# ch347.net
KiCad netlist of a schematic drawn in Altium Designer
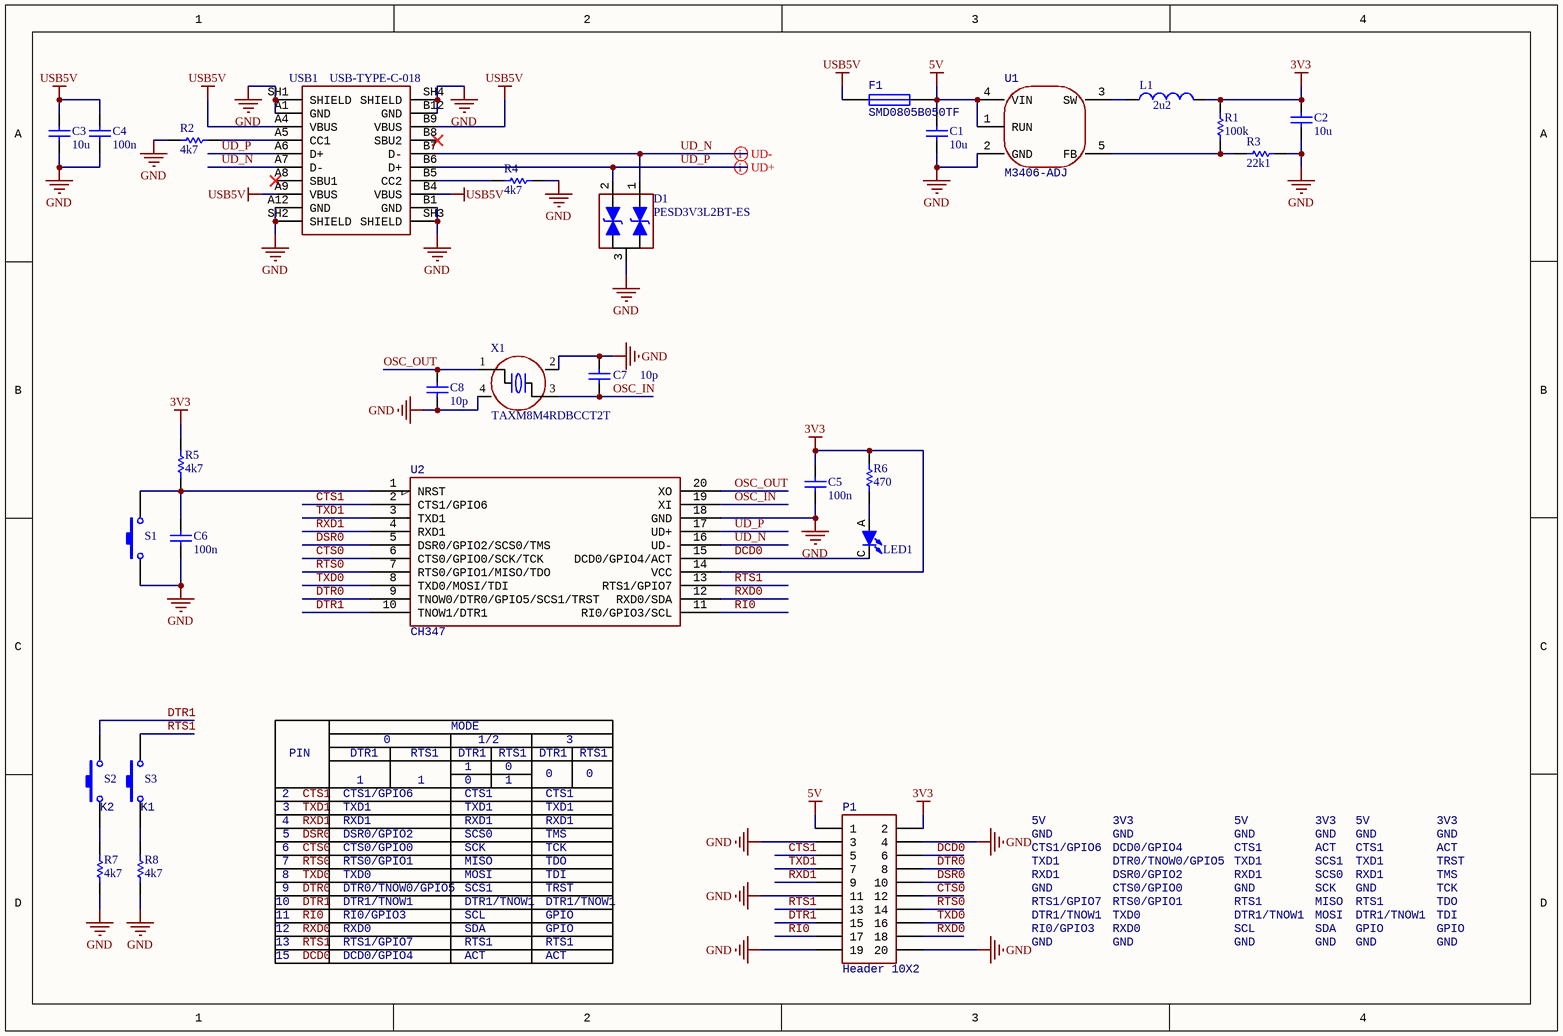
[diagram p0: ch347.SchDoc]

(export (version "E")
  (design (tool "Eeschema 10.0.6"))
  (components
    (comp (ref "C1")
      (value "10u")
      (footprint "footprints:CAPC160X80X90L30N")
      (fields
        (field (name "MPN") "TCC0603X5R106K100CT")
        (field (name "MANUFACTURER") "CCTC(三环)")
        (field (name "Comment") "Capacitor")
      )
      (libsource (lib "std_lib") (part "Capacitor"))
    )
    (comp (ref "C2")
      (value "10u")
      (footprint "footprints:CAPC160X80X90L30N")
      (fields
        (field (name "MPN") "TCC0603X5R106K100CT")
        (field (name "MANUFACTURER") "CCTC(三环)")
        (field (name "Comment") "Capacitor")
      )
      (libsource (lib "std_lib") (part "Capacitor"))
    )
    (comp (ref "C3")
      (value "10u")
      (footprint "footprints:CAPC160X80X90L30N")
      (fields
        (field (name "MPN") "TCC0603X5R106K100CT")
        (field (name "MANUFACTURER") "CCTC(三环)")
        (field (name "Comment") "Capacitor")
      )
      (libsource (lib "std_lib") (part "Capacitor"))
    )
    (comp (ref "C4")
      (value "100n")
      (footprint "footprints:CAPC100X50X55L25N")
      (fields
        (field (name "MPN") "TCC0402X5R104M250AT")
        (field (name "MANUFACTURER") "CCTC(三环)")
        (field (name "Comment") "Capacitor")
      )
      (libsource (lib "std_lib") (part "Capacitor"))
    )
    (comp (ref "C5")
      (value "100n")
      (footprint "footprints:CAPC100X50X55L25N")
      (fields
        (field (name "MPN") "TCC0402X5R104M250AT")
        (field (name "MANUFACTURER") "CCTC(三环)")
        (field (name "Comment") "Capacitor")
      )
      (libsource (lib "std_lib") (part "Capacitor"))
    )
    (comp (ref "C6")
      (value "100n")
      (footprint "footprints:CAPC100X50X55L25N")
      (fields
        (field (name "MPN") "TCC0402X5R104M250AT")
        (field (name "MANUFACTURER") "CCTC(三环)")
        (field (name "Comment") "Capacitor")
      )
      (libsource (lib "std_lib") (part "Capacitor"))
    )
    (comp (ref "C7")
      (value "10p")
      (footprint "footprints:CAPC100X50X55L25N")
      (fields
        (field (name "MPN") "CC0402JRNPO9BN100")
        (field (name "MANUFACTURER") "YAGEO(国巨)")
        (field (name "Comment") "Capacitor")
      )
      (libsource (lib "std_lib") (part "Capacitor"))
    )
    (comp (ref "C8")
      (value "10p")
      (footprint "footprints:CAPC100X50X55L25N")
      (fields
        (field (name "MPN") "CC0402JRNPO9BN100")
        (field (name "MANUFACTURER") "YAGEO(国巨)")
        (field (name "Comment") "Capacitor")
      )
      (libsource (lib "std_lib") (part "Capacitor"))
    )
    (comp (ref "D1")
      (value "PESD3V3L2BT-ES")
      (footprint "footprints:SOT23-3P95_237X111L52X43N")
      (description "2路双向ESD")
      (fields (field (name "MANUFACTURER") "ElecSuper(静芯微)"))
      (libsource (lib "mcontroller") (part "SMC24"))
    )
    (comp (ref "F1")
      (value "SMD0805B050TF")
      (footprint "footprints:FUSC210X135X125L37N")
      (description "Fuse")
      (libsource (lib "Miscellaneous Devices") (part "Fuse 1"))
    )
    (comp (ref "L1")
      (value "2u2")
      (footprint "footprints:INDC200X160X105L60N")
      (fields
        (field (name "MPN") "SFE201610-2R2M")
        (field (name "MANUFACTURER") "DDY(德立)")
        (field (name "Comment") "Inductor")
      )
      (libsource (lib "std_lib") (part "Inductor"))
    )
    (comp (ref "LED1")
      (value "蓝灯 正贴")
      (footprint "footprints:LEDC100X50X45L25N")
      (description "贴片LED")
      (libsource (lib "mcontroller") (part "LED-SMD"))
    )
    (comp (ref "P1")
      (value "Header 10X2")
      (footprint "footprints:HDRV20W63P254_10X2_2540X508H860")
      (description "Header, 10-Pin, Dual row")
      (libsource (lib "Sch") (part "Header 10X2"))
    )
    (comp (ref "R1")
      (value "100k")
      (footprint "footprints:RESC100X50X35L25N")
      (fields
        (field (name "MPN") "RTT021003FTH")
        (field (name "MANUFACTURER") "RALEC(旺诠)")
        (field (name "Comment") "Resistor")
      )
      (libsource (lib "std_lib") (part "Resistor"))
    )
    (comp (ref "R2")
      (value "4k7")
      (footprint "footprints:RESC100X50X35L25N")
      (fields
        (field (name "MPN") "RTT02472JTH")
        (field (name "MANUFACTURER") "RALEC(旺诠)")
        (field (name "Comment") "Resistor")
      )
      (libsource (lib "std_lib") (part "Resistor"))
    )
    (comp (ref "R3")
      (value "22k1")
      (footprint "footprints:RESC100X50X35L25N")
      (fields
        (field (name "MPN") "RTT022212FTH")
        (field (name "MANUFACTURER") "RALEC(旺诠)")
        (field (name "Comment") "Resistor")
      )
      (libsource (lib "std_lib") (part "Resistor"))
    )
    (comp (ref "R4")
      (value "4k7")
      (footprint "footprints:RESC100X50X35L25N")
      (fields
        (field (name "MPN") "RTT02472JTH")
        (field (name "MANUFACTURER") "RALEC(旺诠)")
        (field (name "Comment") "Resistor")
      )
      (libsource (lib "std_lib") (part "Resistor"))
    )
    (comp (ref "R5")
      (value "4k7")
      (footprint "footprints:RESC100X50X35L25N")
      (fields
        (field (name "MPN") "RTT02472JTH")
        (field (name "MANUFACTURER") "RALEC(旺诠)")
        (field (name "Comment") "Resistor")
      )
      (libsource (lib "std_lib") (part "Resistor"))
    )
    (comp (ref "R6")
      (value "470")
      (footprint "footprints:RESC100X50X35L25N")
      (fields
        (field (name "MPN") "RTT02471JTH")
        (field (name "MANUFACTURER") "RALEC(旺诠)")
        (field (name "Comment") "Resistor")
      )
      (libsource (lib "std_lib") (part "Resistor"))
    )
    (comp (ref "R7")
      (value "4k7")
      (footprint "footprints:RESC100X50X35L25N")
      (fields
        (field (name "MPN") "RTT02472JTH")
        (field (name "MANUFACTURER") "RALEC(旺诠)")
        (field (name "Comment") "Resistor")
      )
      (libsource (lib "std_lib") (part "Resistor"))
    )
    (comp (ref "R8")
      (value "4k7")
      (footprint "footprints:RESC100X50X35L25N")
      (fields
        (field (name "MPN") "RTT02472JTH")
        (field (name "MANUFACTURER") "RALEC(旺诠)")
        (field (name "Comment") "Resistor")
      )
      (libsource (lib "std_lib") (part "Resistor"))
    )
    (comp (ref "S1")
      (value "KEY")
      (footprint "footprints:RESRR450W70L600T345H610")
      (description "Switch")
      (libsource (lib "Miscellaneous Devices") (part "SW-PB"))
    )
    (comp (ref "S2")
      (value "KEY")
      (footprint "footprints:RESRR450W70L600T345H610")
      (description "Switch")
      (libsource (lib "Miscellaneous Devices") (part "SW-PB"))
    )
    (comp (ref "S3")
      (value "KEY")
      (footprint "footprints:RESRR450W70L600T345H610")
      (description "Switch")
      (libsource (lib "Miscellaneous Devices") (part "SW-PB"))
    )
    (comp (ref "U1")
      (value "M3406-ADJ")
      (footprint "footprints:SOT23-5P95_280X110L37X40N")
      (description "Vin=2V~6V,800mA,DCDC")
      (fields (field (name "MANUFACTURER") "西安航天民芯"))
      (libsource (lib "Sch") (part "M3406-ADJ"))
    )
    (comp (ref "U2")
      (value "CH347")
      (footprint "Pcb:SOP20P65_650X640X120L60X24N")
      (libsource (lib "Sch") (part "CH347"))
    )
    (comp (ref "USB1")
      (value "USB-TYPE-C-018")
      (footprint "footprints:USB-TYPE-C-018")
      (libsource (lib "Sch") (part "USB-TYPE-C-018"))
    )
    (comp (ref "X1")
      (value "TAXM8M4RDBCCT2T")
      (footprint "footprints:OSCCC320X250X80L90X100N")
      (description "8MHz ±10ppm 10pF")
      (fields (field (name "MANUFACTURER") "TAE(雅晶鑫)"))
      (libsource (lib "mcontroller") (part "X32258MSB4SI"))
    )
  )
  (nets
    (net (code "1") (name "/CTS0") (class "Default")
      (node (ref "P1") (pin "12") (pinfunction "12_12") (pintype "passive"))
      (node (ref "U2") (pin "6") (pinfunction "CTS0/GPIO0/SCK/TCK_6") (pintype "passive"))
    )
    (net (code "2") (name "/CTS1") (class "Default")
      (node (ref "P1") (pin "5") (pinfunction "5_5") (pintype "passive"))
      (node (ref "U2") (pin "2") (pinfunction "CTS1/GPIO6_2") (pintype "passive"))
    )
    (net (code "3") (name "/DCD0") (class "Default")
      (node (ref "LED1") (pin "C") (pinfunction "K_C") (pintype "passive"))
      (node (ref "P1") (pin "6") (pinfunction "6_6") (pintype "passive"))
      (node (ref "U2") (pin "15") (pinfunction "DCD0/GPIO4/ACT_15") (pintype "passive"))
    )
    (net (code "4") (name "/DSR0") (class "Default")
      (node (ref "P1") (pin "10") (pinfunction "10_10") (pintype "passive"))
      (node (ref "U2") (pin "5") (pinfunction "DSR0/GPIO2/SCS0/TMS_5") (pintype "passive"))
    )
    (net (code "5") (name "/DTR0") (class "Default")
      (node (ref "P1") (pin "8") (pinfunction "8_8") (pintype "passive"))
      (node (ref "U2") (pin "9") (pinfunction "TNOW0/DTR0/GPIO5/SCS1/TRST_9") (pintype "passive"))
    )
    (net (code "6") (name "/DTR1") (class "Default")
      (node (ref "P1") (pin "15") (pinfunction "15_15") (pintype "passive"))
      (node (ref "S2") (pin "1") (pinfunction "1_1") (pintype "passive"))
      (node (ref "U2") (pin "10") (pinfunction "TNOW1/DTR1_10") (pintype "passive"))
    )
    (net (code "7") (name "/OSC_IN") (class "Default")
      (node (ref "C7") (pin "1") (pinfunction "1_1") (pintype "passive"))
      (node (ref "U2") (pin "19") (pinfunction "XI_19") (pintype "passive"))
      (node (ref "X1") (pin "3") (pinfunction "3_3") (pintype "passive"))
    )
    (net (code "8") (name "/OSC_OUT") (class "Default")
      (node (ref "C8") (pin "2") (pinfunction "2_2") (pintype "passive"))
      (node (ref "U2") (pin "20") (pinfunction "XO_20") (pintype "passive"))
      (node (ref "X1") (pin "1") (pinfunction "1_1") (pintype "passive"))
    )
    (net (code "9") (name "/RI0") (class "Default")
      (node (ref "P1") (pin "17") (pinfunction "17_17") (pintype "passive"))
      (node (ref "U2") (pin "11") (pinfunction "RI0/GPIO3/SCL_11") (pintype "passive"))
    )
    (net (code "10") (name "/RTS0") (class "Default")
      (node (ref "P1") (pin "14") (pinfunction "14_14") (pintype "passive"))
      (node (ref "U2") (pin "7") (pinfunction "RTS0/GPIO1/MISO/TDO_7") (pintype "passive"))
    )
    (net (code "11") (name "/RTS1") (class "Default")
      (node (ref "P1") (pin "13") (pinfunction "13_13") (pintype "passive"))
      (node (ref "S3") (pin "1") (pinfunction "1_1") (pintype "passive"))
      (node (ref "U2") (pin "13") (pinfunction "RTS1/GPIO7_13") (pintype "passive"))
    )
    (net (code "12") (name "/RXD0") (class "Default")
      (node (ref "P1") (pin "18") (pinfunction "18_18") (pintype "passive"))
      (node (ref "U2") (pin "12") (pinfunction "RXD0/SDA_12") (pintype "passive"))
    )
    (net (code "13") (name "/RXD1") (class "Default")
      (node (ref "P1") (pin "9") (pinfunction "9_9") (pintype "passive"))
      (node (ref "U2") (pin "4") (pinfunction "RXD1_4") (pintype "passive"))
    )
    (net (code "14") (name "/TXD0") (class "Default")
      (node (ref "P1") (pin "16") (pinfunction "16_16") (pintype "passive"))
      (node (ref "U2") (pin "8") (pinfunction "TXD0/MOSI/TDI_8") (pintype "passive"))
    )
    (net (code "15") (name "/TXD1") (class "Default")
      (node (ref "P1") (pin "7") (pinfunction "7_7") (pintype "passive"))
      (node (ref "U2") (pin "3") (pinfunction "TXD1_3") (pintype "passive"))
    )
    (net (code "16") (name "/UD_N") (class "Default")
      (node (ref "D1") (pin "1") (pinfunction "1_1") (pintype "passive"))
      (node (ref "U2") (pin "16") (pinfunction "UD-_16") (pintype "passive"))
      (node (ref "USB1") (pin "A7") (pinfunction "D-_A7") (pintype "passive"))
      (node (ref "USB1") (pin "B7") (pinfunction "D-_B7") (pintype "passive"))
    )
    (net (code "17") (name "/UD_P") (class "Default")
      (node (ref "D1") (pin "2") (pinfunction "2_2") (pintype "passive"))
      (node (ref "U2") (pin "17") (pinfunction "UD+_17") (pintype "passive"))
      (node (ref "USB1") (pin "A6") (pinfunction "D+_A6") (pintype "passive"))
      (node (ref "USB1") (pin "B6") (pinfunction "D+_B6") (pintype "passive"))
    )
    (net (code "18") (name "3V3") (class "Default")
      (node (ref "C2") (pin "2") (pinfunction "2_2") (pintype "passive"))
      (node (ref "C5") (pin "2") (pinfunction "2_2") (pintype "passive"))
      (node (ref "L1") (pin "2") (pinfunction "2_2") (pintype "passive"))
      (node (ref "P1") (pin "2") (pinfunction "2_2") (pintype "passive"))
      (node (ref "R1") (pin "2") (pinfunction "2_2") (pintype "passive"))
      (node (ref "R5") (pin "1") (pinfunction "1_1") (pintype "passive"))
      (node (ref "R6") (pin "1") (pinfunction "1_1") (pintype "passive"))
      (node (ref "U2") (pin "14") (pinfunction "VCC_14") (pintype "passive"))
    )
    (net (code "19") (name "5V") (class "Default")
      (node (ref "C1") (pin "2") (pinfunction "2_2") (pintype "passive"))
      (node (ref "F1") (pin "2") (pinfunction "2_2") (pintype "passive"))
      (node (ref "P1") (pin "1") (pinfunction "1_1") (pintype "passive"))
      (node (ref "U1") (pin "1") (pinfunction "RUN_1") (pintype "passive"))
      (node (ref "U1") (pin "4") (pinfunction "VIN_4") (pintype "passive"))
    )
    (net (code "20") (name "GND") (class "Default")
      (node (ref "C1") (pin "1") (pinfunction "1_1") (pintype "passive"))
      (node (ref "C2") (pin "1") (pinfunction "1_1") (pintype "passive"))
      (node (ref "C3") (pin "1") (pinfunction "1_1") (pintype "passive"))
      (node (ref "C4") (pin "1") (pinfunction "1_1") (pintype "passive"))
      (node (ref "C5") (pin "1") (pinfunction "1_1") (pintype "passive"))
      (node (ref "C6") (pin "1") (pinfunction "1_1") (pintype "passive"))
      (node (ref "C7") (pin "2") (pinfunction "2_2") (pintype "passive"))
      (node (ref "C8") (pin "1") (pinfunction "1_1") (pintype "passive"))
      (node (ref "D1") (pin "3") (pinfunction "3_3") (pintype "passive"))
      (node (ref "P1") (pin "11") (pinfunction "11_11") (pintype "passive"))
      (node (ref "P1") (pin "19") (pinfunction "19_19") (pintype "passive"))
      (node (ref "P1") (pin "20") (pinfunction "20_20") (pintype "passive"))
      (node (ref "P1") (pin "3") (pinfunction "3_3") (pintype "passive"))
      (node (ref "P1") (pin "4") (pinfunction "4_4") (pintype "passive"))
      (node (ref "R2") (pin "2") (pinfunction "2_2") (pintype "passive"))
      (node (ref "R3") (pin "1") (pinfunction "1_1") (pintype "passive"))
      (node (ref "R4") (pin "1") (pinfunction "1_1") (pintype "passive"))
      (node (ref "R7") (pin "2") (pinfunction "2_2") (pintype "passive"))
      (node (ref "R8") (pin "2") (pinfunction "2_2") (pintype "passive"))
      (node (ref "S1") (pin "2") (pinfunction "2_2") (pintype "passive"))
      (node (ref "U1") (pin "2") (pinfunction "GND_2") (pintype "passive"))
      (node (ref "U2") (pin "18") (pinfunction "GND_18") (pintype "passive"))
      (node (ref "USB1") (pin "A1") (pinfunction "GND_A1") (pintype "passive"))
      (node (ref "USB1") (pin "A12") (pinfunction "GND_A12") (pintype "passive"))
      (node (ref "USB1") (pin "B1") (pinfunction "GND_B1") (pintype "passive"))
      (node (ref "USB1") (pin "B12") (pinfunction "GND_B12") (pintype "passive"))
      (node (ref "USB1") (pin "SH1") (pinfunction "SHIELD_SH1") (pintype "passive"))
      (node (ref "USB1") (pin "SH2") (pinfunction "SHIELD_SH2") (pintype "passive"))
      (node (ref "USB1") (pin "SH3") (pinfunction "SHIELD_SH3") (pintype "passive"))
      (node (ref "USB1") (pin "SH4") (pinfunction "SHIELD_SH4") (pintype "passive"))
      (node (ref "X1") (pin "2") (pinfunction "GND_2") (pintype "passive"))
      (node (ref "X1") (pin "4") (pinfunction "GND_4") (pintype "passive"))
    )
    (net (code "21") (name "Net-(LED1-PadA)") (class "Default")
      (node (ref "LED1") (pin "A") (pinfunction "A_A") (pintype "passive"))
      (node (ref "R6") (pin "2") (pinfunction "2_2") (pintype "passive"))
    )
    (net (code "22") (name "Net-(R7-Pad1)") (class "Default")
      (node (ref "R7") (pin "1") (pinfunction "1_1") (pintype "passive"))
      (node (ref "S2") (pin "2") (pinfunction "2_2") (pintype "passive"))
    )
    (net (code "23") (name "Net-(R8-Pad1)") (class "Default")
      (node (ref "R8") (pin "1") (pinfunction "1_1") (pintype "passive"))
      (node (ref "S3") (pin "2") (pinfunction "2_2") (pintype "passive"))
    )
    (net (code "24") (name "Net-(U1-FB)") (class "Default")
      (node (ref "R1") (pin "1") (pinfunction "1_1") (pintype "passive"))
      (node (ref "R3") (pin "2") (pinfunction "2_2") (pintype "passive"))
      (node (ref "U1") (pin "5") (pinfunction "FB_5") (pintype "passive"))
    )
    (net (code "25") (name "Net-(U1-SW)") (class "Default")
      (node (ref "L1") (pin "1") (pinfunction "1_1") (pintype "passive"))
      (node (ref "U1") (pin "3") (pinfunction "SW_3") (pintype "passive"))
    )
    (net (code "26") (name "Net-(U2-NRST)") (class "Default")
      (node (ref "C6") (pin "2") (pinfunction "2_2") (pintype "passive"))
      (node (ref "R5") (pin "2") (pinfunction "2_2") (pintype "passive"))
      (node (ref "S1") (pin "1") (pinfunction "1_1") (pintype "passive"))
      (node (ref "U2") (pin "1") (pinfunction "NRST_1") (pintype "passive"))
    )
    (net (code "27") (name "Net-(USB1-CC1)") (class "Default")
      (node (ref "R2") (pin "1") (pinfunction "1_1") (pintype "passive"))
      (node (ref "USB1") (pin "A5") (pinfunction "CC1_A5") (pintype "passive"))
    )
    (net (code "28") (name "Net-(USB1-CC2)") (class "Default")
      (node (ref "R4") (pin "2") (pinfunction "2_2") (pintype "passive"))
      (node (ref "USB1") (pin "B5") (pinfunction "CC2_B5") (pintype "passive"))
    )
    (net (code "29") (name "USB5V") (class "Default")
      (node (ref "C3") (pin "2") (pinfunction "2_2") (pintype "passive"))
      (node (ref "C4") (pin "2") (pinfunction "2_2") (pintype "passive"))
      (node (ref "F1") (pin "1") (pinfunction "1_1") (pintype "passive"))
      (node (ref "USB1") (pin "A4") (pinfunction "VBUS_A4") (pintype "passive"))
      (node (ref "USB1") (pin "A9") (pinfunction "VBUS_A9") (pintype "passive"))
      (node (ref "USB1") (pin "B4") (pinfunction "VBUS_B4") (pintype "passive"))
      (node (ref "USB1") (pin "B9") (pinfunction "VBUS_B9") (pintype "passive"))
    )
    (net (code "30") (name "unconnected-(USB1-SBU1-PadA8)") (class "Default")
      (node (ref "USB1") (pin "A8") (pinfunction "SBU1_A8") (pintype "passive+no_connect"))
    )
    (net (code "31") (name "unconnected-(USB1-SBU2-PadB8)") (class "Default")
      (node (ref "USB1") (pin "B8") (pinfunction "SBU2_B8") (pintype "passive+no_connect"))
    )
  )
)
